# Power_meter.net
KiCad netlist of a schematic drawn in Altium Designer
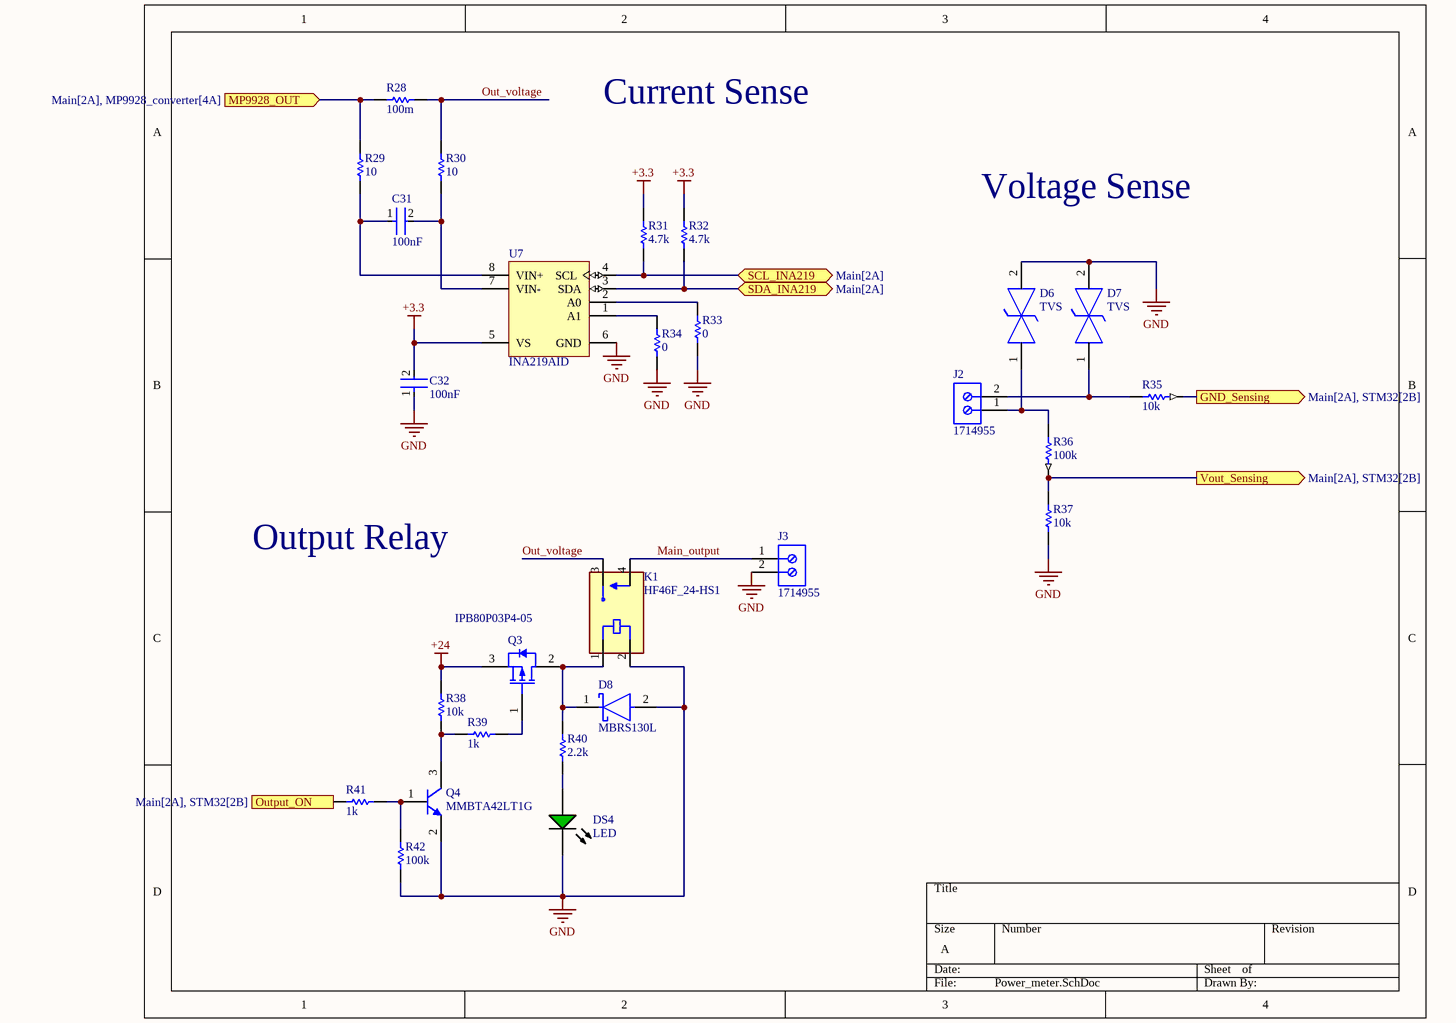
[diagram p0: Power_meter.SchDoc]

(export (version "E")
  (design (tool "Eeschema 10.0.6"))
  (components
    (comp (ref "C31")
      (value "100nF")
      (footprint "FP-0805-L_2_01_0_2-W_1_25-IPC_B")
      (description "General Purpose Ceramic Capacitor, 0805, 100nF, 10%, X7R, 15%, 100V")
      (fields (field (name "VOLTAGE") "100V") (field (name "TOLERANCE") "10%"))
      (libsource (lib "Altium Content Vault") (part "b4654b650e69147ec39a6b967a45e02"))
    )
    (comp (ref "C32")
      (value "100nF")
      (footprint "FP-0805-L_2_01_0_2-W_1_25-IPC_B")
      (description "General Purpose Ceramic Capacitor, 0805, 100nF, 10%, X7R, 15%, 100V")
      (fields (field (name "VOLTAGE") "100V") (field (name "TOLERANCE") "10%"))
      (libsource (lib "Altium Content Vault") (part "b4654b650e69147ec39a6b967a45e02"))
    )
    (comp (ref "D6")
      (value "TVS")
      (footprint "FP-SMB-MFG")
      (description "TVS DIODE 28.2V 59V SMB")
      (fields
        (field (name "OCTOPART") "https://octopart.com/sm6t33ca-stmicroelectronics-55399331")
        (field (name "MANUFACTURER PART NUMBER") "SM6T33CA")
      )
      (libsource (lib "Altium Content Vault") (part "ebc102d6f37e12f28676a717a4d7ff6"))
    )
    (comp (ref "D7")
      (value "TVS")
      (footprint "FP-SMB-MFG")
      (description "TVS DIODE 28.2V 59V SMB")
      (fields
        (field (name "OCTOPART") "https://octopart.com/sm6t33ca-stmicroelectronics-55399331")
        (field (name "MANUFACTURER PART NUMBER") "SM6T33CA")
      )
      (libsource (lib "Altium Content Vault") (part "ebc102d6f37e12f28676a717a4d7ff6"))
    )
    (comp (ref "D8")
      (value "MBRS130L")
      (footprint "FP-403AF-MFG")
      (description "MBRS130L Rectifier Diode, Schottky, 1 Phase, 1 Element, 2A, 30V V(RRM), Silicon, DO-214AA")
      (libsource (lib "Altium Content Vault") (part "1d6ec82d83fb6aee721767c19dac4b9"))
    )
    (comp (ref "DS4")
      (value "LED")
      (footprint "AVAG-HSMX-C170_V")
      (description "Chip LED, Green, 2.2 V, -40 to 85 degC, 2-Pin SMD, Pb-Free, Tape and Reel")
      (fields (field (name "MANUFACTURER") "Avago"))
      (libsource (lib "Altium Content Vault") (part "LED_GREEN_A1K2-2"))
    )
    (comp (ref "J2")
      (value "1714955")
      (footprint "PHOE-1714955_V")
      (description "PC Terminal Block, Pitch 6.35 mm, 1 x 2 Position, Height 21.5 mm, Tail Lenght 5.1 mm, RoHS, Bulk")
      (fields (field (name "MANUFACTURER") "Phoenix Contact"))
      (libsource (lib "Altium Content Vault") (part "CN-1P-F-TB2"))
    )
    (comp (ref "J3")
      (value "1714955")
      (footprint "PHOE-1714955_V")
      (description "PC Terminal Block, Pitch 6.35 mm, 1 x 2 Position, Height 21.5 mm, Tail Lenght 5.1 mm, RoHS, Bulk")
      (fields (field (name "MANUFACTURER") "Phoenix Contact"))
      (libsource (lib "Altium Content Vault") (part "CN-1P-F-TB2"))
    )
    (comp (ref "K1")
      (value "HF46F_24-HS1")
      (footprint "RELAY_HF46F_005-HS1")
      (description "Relay: electromagnetic; SPST-NO; Ucoil: 24VDC; 5A/250VAC; 5A/30VDC")
      (fields (field (name "MF") "Hongfa") (field (name "MP") "HF46F/005-HS1"))
      (libsource (lib "HF46F_005-HS1") (part "HF46F_005-HS1"))
    )
    (comp (ref "Q3")
      (value "IPB80P03P4-05")
      (footprint "INF-PG-TO263-3-2_N")
      (description "OptiMOS-P2 Power-Transistor, -30 V VDS, -80 A ID, PG-TO263-3-2, Reel, Green")
      (fields (field (name "MANUFACTURER") "Infineon"))
      (libsource (lib "Altium Content Vault") (part "INF-MOSFET-P-3"))
    )
    (comp (ref "Q4")
      (value "MMBTA42LT1G")
      (footprint "ONSC-SOT-23-3-318-08_V")
      (description "High Voltage Transistor, NPN Silicon, 3-Pin SOT-23, Pb-Free, Tape and Reel")
      (fields (field (name "MANUFACTURER") "On Semiconductor"))
      (libsource (lib "Altium Content Vault") (part "ONSC-NPN-B1E2C3-3"))
    )
    (comp (ref "R28")
      (value "100m")
      (footprint "RESC3216X70X50NL05T20")
      (description "Shunt resistor")
      (fields (field (name "PART NUMBER") "ERJ8BSFR10V") (field (name "MANUFACTURER") "Panasonic"))
      (libsource (lib "Altium Content Vault") (part "RES"))
    )
    (comp (ref "R29")
      (value "10")
      (footprint "RESC2013X50X30LL20T20")
      (fields (field (name "MANUFACTURER") "Vishay Dale") (field (name "PART NUMBER") "CRCW08050000Z0EA"))
      (libsource (lib "Altium Content Vault") (part "RES"))
    )
    (comp (ref "R30")
      (value "10")
      (footprint "RESC2013X50X30LL20T20")
      (fields (field (name "MANUFACTURER") "Vishay Dale") (field (name "PART NUMBER") "CRCW08050000Z0EA"))
      (libsource (lib "Altium Content Vault") (part "RES"))
    )
    (comp (ref "R31")
      (value "4.7k")
      (footprint "RESC2013X50X30LL20T20")
      (fields (field (name "MANUFACTURER") "Vishay Dale") (field (name "PART NUMBER") "CRCW08050000Z0EA"))
      (libsource (lib "Altium Content Vault") (part "RES"))
    )
    (comp (ref "R32")
      (value "4.7k")
      (footprint "RESC2013X50X30LL20T20")
      (fields (field (name "MANUFACTURER") "Vishay Dale") (field (name "PART NUMBER") "CRCW08050000Z0EA"))
      (libsource (lib "Altium Content Vault") (part "RES"))
    )
    (comp (ref "R33")
      (value "0")
      (footprint "RESC2013X50X30LL20T20")
      (fields (field (name "MANUFACTURER") "Vishay Dale") (field (name "PART NUMBER") "CRCW08050000Z0EA"))
      (libsource (lib "Altium Content Vault") (part "RES"))
    )
    (comp (ref "R34")
      (value "0")
      (footprint "RESC2013X50X30LL20T20")
      (fields (field (name "MANUFACTURER") "Vishay Dale") (field (name "PART NUMBER") "CRCW08050000Z0EA"))
      (libsource (lib "Altium Content Vault") (part "RES"))
    )
    (comp (ref "R35")
      (value "10k")
      (footprint "RESC2013X50X30LL20T20")
      (fields (field (name "MANUFACTURER") "Vishay Dale") (field (name "PART NUMBER") "CRCW08050000Z0EA"))
      (libsource (lib "") (part "RES_2"))
    )
    (comp (ref "R36")
      (value "100k")
      (footprint "RESC2013X50X30LL20T20")
      (fields (field (name "MANUFACTURER") "Vishay Dale") (field (name "PART NUMBER") "CRCW08050000Z0EA"))
      (libsource (lib "") (part "RES_1"))
    )
    (comp (ref "R37")
      (value "10k")
      (footprint "RESC2013X50X30LL20T20")
      (fields (field (name "MANUFACTURER") "Vishay Dale") (field (name "PART NUMBER") "CRCW08050000Z0EA"))
      (libsource (lib "Altium Content Vault") (part "RES"))
    )
    (comp (ref "R38")
      (value "10k")
      (footprint "RESC2013X50X30LL20T20")
      (fields (field (name "MANUFACTURER") "Vishay Dale") (field (name "PART NUMBER") "CRCW08050000Z0EA"))
      (libsource (lib "Altium Content Vault") (part "RES"))
    )
    (comp (ref "R39")
      (value "1k")
      (footprint "RESC2013X50X30LL20T20")
      (fields (field (name "MANUFACTURER") "Vishay Dale") (field (name "PART NUMBER") "CRCW08050000Z0EA"))
      (libsource (lib "Altium Content Vault") (part "RES"))
    )
    (comp (ref "R40")
      (value "2.2k")
      (footprint "RESC2013X50X30LL20T20")
      (fields (field (name "MANUFACTURER") "Vishay Dale") (field (name "PART NUMBER") "CRCW08050000Z0EA"))
      (libsource (lib "Altium Content Vault") (part "RES"))
    )
    (comp (ref "R41")
      (value "1k")
      (footprint "RESC2013X50X30LL20T20")
      (fields (field (name "MANUFACTURER") "Vishay Dale") (field (name "PART NUMBER") "CRCW08050000Z0EA"))
      (libsource (lib "Altium Content Vault") (part "RES"))
    )
    (comp (ref "R42")
      (value "100k")
      (footprint "RESC2013X50X30LL20T20")
      (fields (field (name "MANUFACTURER") "Vishay Dale") (field (name "PART NUMBER") "CRCW08050000Z0EA"))
      (libsource (lib "Altium Content Vault") (part "RES"))
    )
    (comp (ref "U7")
      (value "INA219AID")
      (footprint "D0008A_N")
      (fields (field (name "MANUFACTURER") "Texas Instruments"))
      (libsource (lib "Altium Content Vault") (part "TI-INA219D8"))
    )
  )
  (nets
    (net (code "1") (name "+3.3") (class "Default")
      (node (ref "C32") (pin "2") (pinfunction "2_2") (pintype "passive"))
      (node (ref "R31") (pin "2") (pinfunction "2_2") (pintype "passive"))
      (node (ref "R32") (pin "2") (pinfunction "2_2") (pintype "passive"))
      (node (ref "U7") (pin "5") (pinfunction "VS_5") (pintype "power_in"))
    )
    (net (code "2") (name "+24") (class "Default")
      (node (ref "Q3") (pin "3") (pinfunction "SOURCE_3") (pintype "passive"))
      (node (ref "R38") (pin "2") (pinfunction "2_2") (pintype "passive"))
    )
    (net (code "3") (name "/GND_Sensing") (class "Default")
      (node (ref "R35") (pin "1") (pinfunction "1_1") (pintype "output"))
    )
    (net (code "4") (name "/MP9928_OUT") (class "Default")
      (node (ref "R28") (pin "1") (pinfunction "1_1") (pintype "passive"))
      (node (ref "R29") (pin "2") (pinfunction "2_2") (pintype "passive"))
    )
    (net (code "5") (name "/Main_output") (class "Default")
      (node (ref "J3") (pin "1") (pinfunction "1_1") (pintype "passive"))
      (node (ref "K1") (pin "4") (pinfunction "NO_4") (pintype "passive"))
    )
    (net (code "6") (name "/Out_voltage") (class "Default")
      (node (ref "K1") (pin "3") (pinfunction "COM_3") (pintype "passive"))
      (node (ref "R28") (pin "2") (pinfunction "2_2") (pintype "passive"))
      (node (ref "R30") (pin "2") (pinfunction "2_2") (pintype "passive"))
    )
    (net (code "7") (name "/Output_ON") (class "Default")
      (node (ref "R41") (pin "1") (pinfunction "1_1") (pintype "passive"))
    )
    (net (code "8") (name "/SCL_INA219") (class "Default")
      (node (ref "R31") (pin "1") (pinfunction "1_1") (pintype "passive"))
      (node (ref "U7") (pin "4") (pinfunction "SCL_4") (pintype "bidirectional"))
    )
    (net (code "9") (name "/SDA_INA219") (class "Default")
      (node (ref "R32") (pin "1") (pinfunction "1_1") (pintype "passive"))
      (node (ref "U7") (pin "3") (pinfunction "SDA_3") (pintype "bidirectional"))
    )
    (net (code "10") (name "/Vout_Sensing") (class "Default")
      (node (ref "R36") (pin "2") (pinfunction "2_2") (pintype "output"))
      (node (ref "R37") (pin "1") (pinfunction "1_1") (pintype "passive"))
    )
    (net (code "11") (name "GND") (class "Default")
      (node (ref "C32") (pin "1") (pinfunction "1_1") (pintype "passive"))
      (node (ref "D6") (pin "2") (pinfunction "2_2") (pintype "passive"))
      (node (ref "D7") (pin "2") (pinfunction "2_2") (pintype "passive"))
      (node (ref "D8") (pin "2") (pinfunction "A_2") (pintype "passive"))
      (node (ref "DS4") (pin "2") (pinfunction "K_2") (pintype "passive"))
      (node (ref "J3") (pin "2") (pinfunction "2_2") (pintype "passive"))
      (node (ref "K1") (pin "2") (pinfunction "COIL2_2") (pintype "passive"))
      (node (ref "Q4") (pin "2") (pinfunction "E_2") (pintype "passive"))
      (node (ref "R33") (pin "1") (pinfunction "1_1") (pintype "passive"))
      (node (ref "R34") (pin "1") (pinfunction "1_1") (pintype "passive"))
      (node (ref "R37") (pin "2") (pinfunction "2_2") (pintype "passive"))
      (node (ref "R42") (pin "1") (pinfunction "1_1") (pintype "passive"))
      (node (ref "U7") (pin "6") (pinfunction "GND_6") (pintype "power_in"))
    )
    (net (code "12") (name "Net-(D6-Pad1)") (class "Default")
      (node (ref "D6") (pin "1") (pinfunction "1_1") (pintype "passive"))
      (node (ref "J2") (pin "1") (pinfunction "1_1") (pintype "passive"))
      (node (ref "R36") (pin "1") (pinfunction "1_1") (pintype "passive"))
    )
    (net (code "13") (name "Net-(D7-Pad1)") (class "Default")
      (node (ref "D7") (pin "1") (pinfunction "1_1") (pintype "passive"))
      (node (ref "J2") (pin "2") (pinfunction "2_2") (pintype "passive"))
      (node (ref "R35") (pin "2") (pinfunction "2_2") (pintype "passive"))
    )
    (net (code "14") (name "Net-(D8-C)") (class "Default")
      (node (ref "D8") (pin "1") (pinfunction "C_1") (pintype "passive"))
      (node (ref "K1") (pin "1") (pinfunction "COIL1_1") (pintype "passive"))
      (node (ref "Q3") (pin "2") (pinfunction "DRAIN_2") (pintype "passive"))
      (node (ref "R40") (pin "2") (pinfunction "2_2") (pintype "passive"))
    )
    (net (code "15") (name "Net-(DS4-A)") (class "Default")
      (node (ref "DS4") (pin "1") (pinfunction "A_1") (pintype "passive"))
      (node (ref "R40") (pin "1") (pinfunction "1_1") (pintype "passive"))
    )
    (net (code "16") (name "Net-(Q3-GATE)") (class "Default")
      (node (ref "Q3") (pin "1") (pinfunction "GATE_1") (pintype "passive"))
      (node (ref "R39") (pin "2") (pinfunction "2_2") (pintype "passive"))
    )
    (net (code "17") (name "Net-(Q4-B)") (class "Default")
      (node (ref "Q4") (pin "1") (pinfunction "B_1") (pintype "passive"))
      (node (ref "R41") (pin "2") (pinfunction "2_2") (pintype "passive"))
      (node (ref "R42") (pin "2") (pinfunction "2_2") (pintype "passive"))
    )
    (net (code "18") (name "Net-(Q4-C)") (class "Default")
      (node (ref "Q4") (pin "3") (pinfunction "C_3") (pintype "passive"))
      (node (ref "R38") (pin "1") (pinfunction "1_1") (pintype "passive"))
      (node (ref "R39") (pin "1") (pinfunction "1_1") (pintype "passive"))
    )
    (net (code "19") (name "Net-(U7-A0)") (class "Default")
      (node (ref "R33") (pin "2") (pinfunction "2_2") (pintype "passive"))
      (node (ref "U7") (pin "2") (pinfunction "A0_2") (pintype "passive"))
    )
    (net (code "20") (name "Net-(U7-A1)") (class "Default")
      (node (ref "R34") (pin "2") (pinfunction "2_2") (pintype "passive"))
      (node (ref "U7") (pin "1") (pinfunction "A1_1") (pintype "passive"))
    )
    (net (code "21") (name "Net-(U7-VIN+)") (class "Default")
      (node (ref "C31") (pin "1") (pinfunction "1_1") (pintype "passive"))
      (node (ref "R29") (pin "1") (pinfunction "1_1") (pintype "passive"))
      (node (ref "U7") (pin "8") (pinfunction "VIN+_8") (pintype "passive"))
    )
    (net (code "22") (name "Net-(U7-VIN-)") (class "Default")
      (node (ref "C31") (pin "2") (pinfunction "2_2") (pintype "passive"))
      (node (ref "R30") (pin "1") (pinfunction "1_1") (pintype "passive"))
      (node (ref "U7") (pin "7") (pinfunction "VIN-_7") (pintype "passive"))
    )
  )
)
